# LB_BIT_1IN_1OUT-XXLWIDE-v03_1_1x.net
KiCad netlist of a schematic drawn in EAGLE
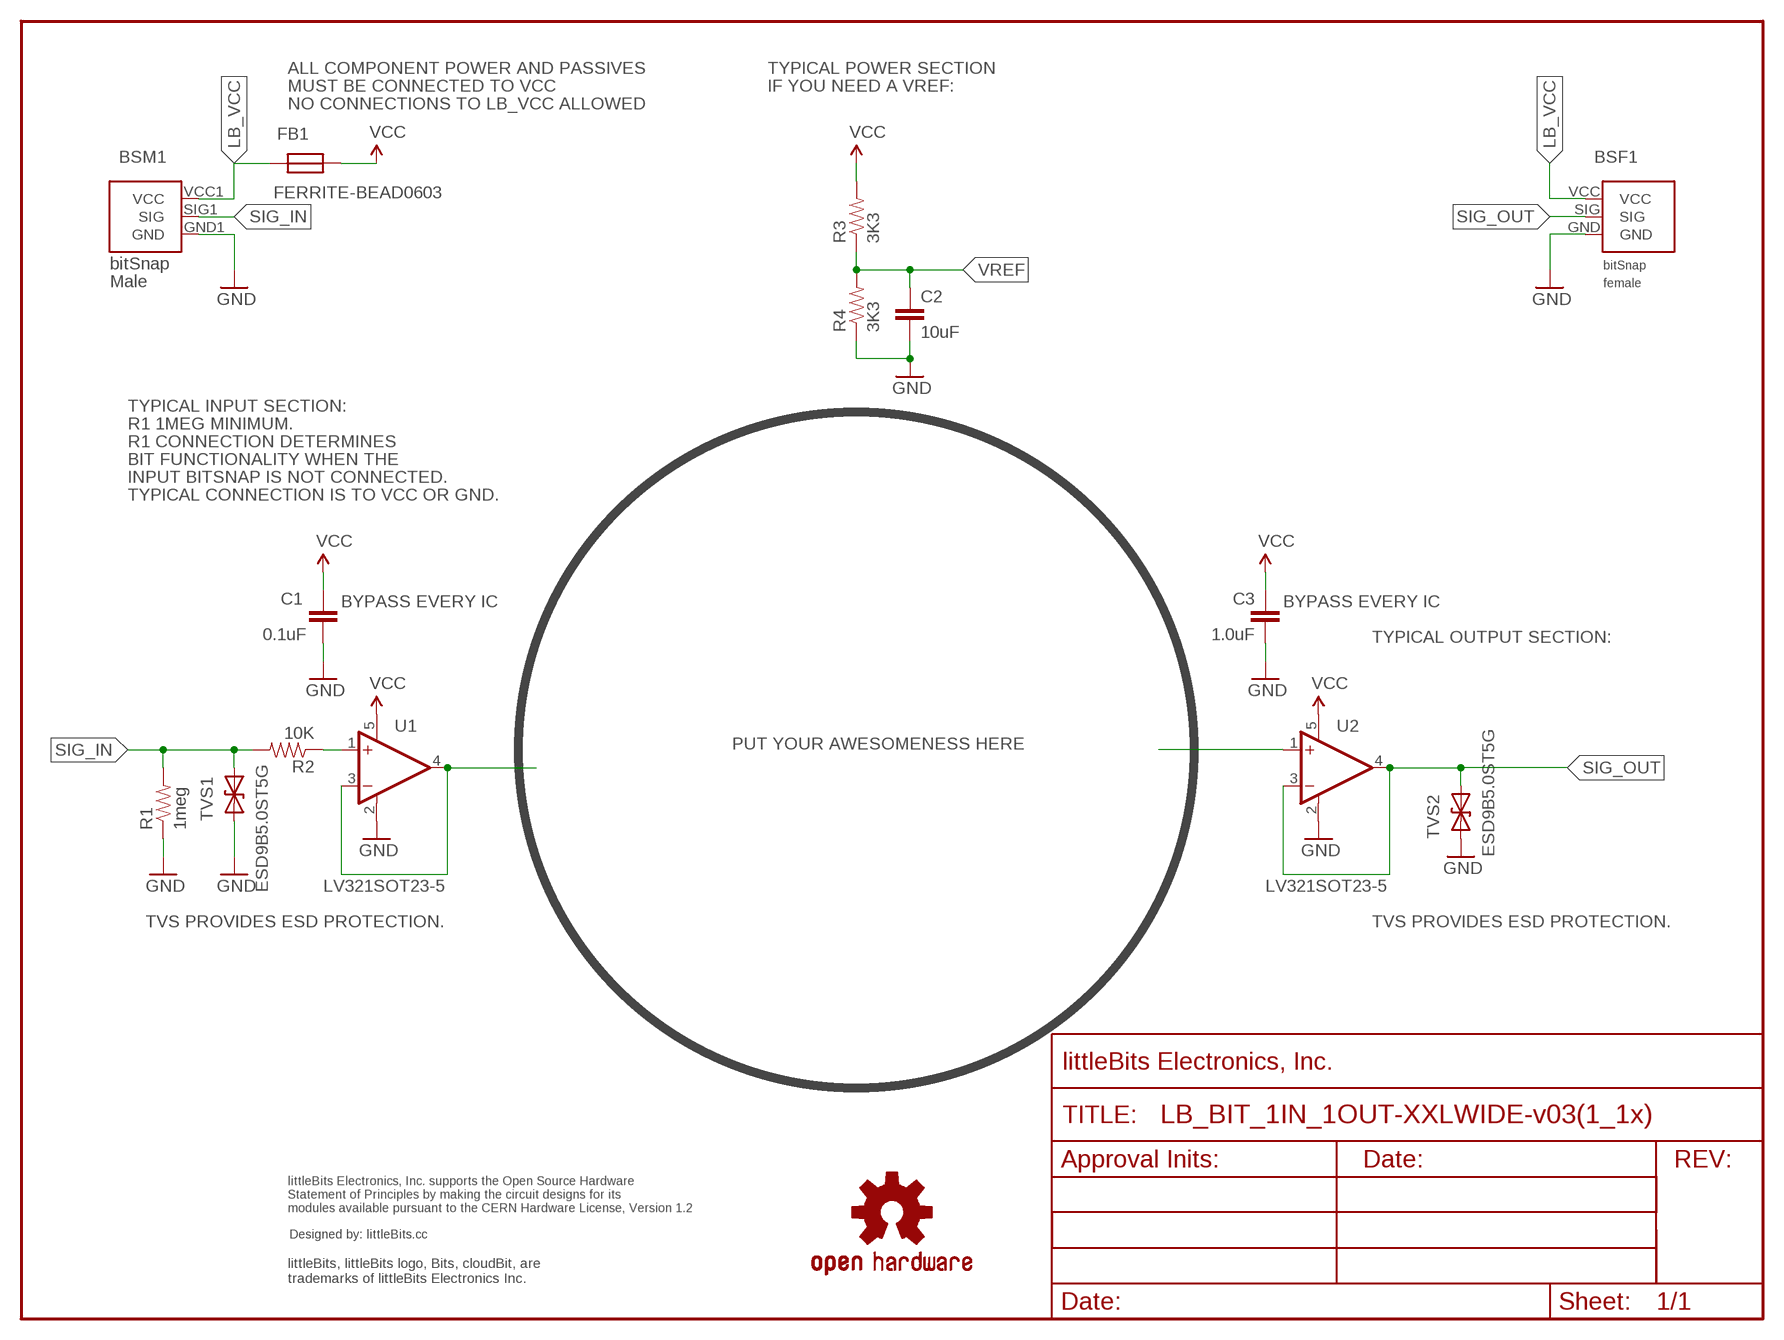
[diagram p0: schematic, sheet 1]

(export (version "E")
  (design (tool "Eeschema 10.0.6"))
  (components
    (comp (ref "BSF1")
      (value "BITSNAP_V03_FEMALE")
      (footprint "eagle-import:BITSNAP_V03_FEMALE")
      (libsource (lib "eagle-import") (part "BITSNAP_V03_FEMALE"))
    )
    (comp (ref "BSM1")
      (value "BITSNAP_V03_MALE")
      (footprint "eagle-import:BITSNAP_V03_MALE")
      (libsource (lib "eagle-import") (part "BITSNAP_V03_MALE"))
    )
    (comp (ref "C1")
      (value "0.1uF")
      (footprint "eagle-import:CAP-0603")
      (libsource (lib "eagle-import") (part "CAPCAP-0603"))
    )
    (comp (ref "C2")
      (value "10uF")
      (footprint "eagle-import:CAP-0603")
      (libsource (lib "eagle-import") (part "CAPCAP-0603"))
    )
    (comp (ref "C3")
      (value "1.0uF")
      (footprint "eagle-import:CAP-0603")
      (libsource (lib "eagle-import") (part "CAPCAP-0603"))
    )
    (comp (ref "FB1")
      (value "FERRITE-BEAD0603")
      (footprint "eagle-import:R0603")
      (libsource (lib "eagle-import") (part "FERRITE-BEAD0603"))
    )
    (comp (ref "R1")
      (value "1meg")
      (footprint "eagle-import:RES-0603")
      (libsource (lib "eagle-import") (part "RESISTOR0603"))
    )
    (comp (ref "R2")
      (value "10K")
      (footprint "eagle-import:RES-0603")
      (libsource (lib "eagle-import") (part "RESISTOR0603"))
    )
    (comp (ref "R3")
      (value "3K3")
      (footprint "eagle-import:RES-0603")
      (libsource (lib "eagle-import") (part "RESISTOR0603"))
    )
    (comp (ref "R4")
      (value "3K3")
      (footprint "eagle-import:RES-0603")
      (libsource (lib "eagle-import") (part "RESISTOR0603"))
    )
    (comp (ref "TVS1")
      (value "ESD9B5.0ST5G")
      (footprint "eagle-import:SOD-923")
      (libsource (lib "eagle-import") (part "DIODE-TVSSOD-923"))
    )
    (comp (ref "TVS2")
      (value "ESD9B5.0ST5G")
      (footprint "eagle-import:SOD-923")
      (libsource (lib "eagle-import") (part "DIODE-TVSSOD-923"))
    )
    (comp (ref "U$1")
      (value "OSHW-LOGOL")
      (footprint "eagle-import:OSHW-LOGO-L")
      (libsource (lib "eagle-import") (part "OSHW-LOGOL"))
    )
    (comp (ref "U$2")
      (value "OSHWCREDIT")
      (footprint "eagle-import:OSHWCREDIT")
      (libsource (lib "eagle-import") (part "OSHWCREDIT"))
    )
    (comp (ref "U$5")
      (value "FRAME-LETTER-OHWOHW")
      (footprint "eagle-import:FABDWG01-OHW")
      (libsource (lib "eagle-import") (part "FRAME-LETTER-OHWOHW"))
    )
    (comp (ref "U1")
      (value "LV321SOT23-5")
      (footprint "eagle-import:SOT23-5")
      (libsource (lib "eagle-import") (part "LV321SOT23-5"))
    )
    (comp (ref "U2")
      (value "LV321SOT23-5")
      (footprint "eagle-import:SOT23-5")
      (libsource (lib "eagle-import") (part "LV321SOT23-5"))
    )
  )
  (nets
    (net (code "1") (name "GND") (class "Default")
      (node (ref "BSF1") (pin "GND") (pinfunction "GND_GND") (pintype "bidirectional"))
      (node (ref "BSM1") (pin "GND1") (pinfunction "GND_GND1") (pintype "bidirectional"))
      (node (ref "C1") (pin "2") (pinfunction "2_2") (pintype "passive"))
      (node (ref "C2") (pin "2") (pinfunction "2_2") (pintype "passive"))
      (node (ref "C3") (pin "1") (pinfunction "1_1") (pintype "passive"))
      (node (ref "R1") (pin "1") (pinfunction "1_1") (pintype "passive"))
      (node (ref "R4") (pin "1") (pinfunction "1_1") (pintype "passive"))
      (node (ref "TVS1") (pin "1") (pinfunction "A_1") (pintype "passive"))
      (node (ref "TVS2") (pin "1") (pinfunction "A_1") (pintype "passive"))
      (node (ref "U1") (pin "2") (pinfunction "V-_2") (pintype "power_in"))
      (node (ref "U2") (pin "2") (pinfunction "V-_2") (pintype "power_in"))
    )
    (net (code "2") (name "LB_VCC") (class "Default")
      (node (ref "BSF1") (pin "VCC") (pinfunction "VCC_VCC") (pintype "bidirectional"))
      (node (ref "BSM1") (pin "VCC1") (pinfunction "VCC_VCC1") (pintype "bidirectional"))
      (node (ref "FB1") (pin "2") (pinfunction "P$2_2") (pintype "bidirectional"))
    )
    (net (code "3") (name "Net-(U1-+IN)") (class "Default")
      (node (ref "R2") (pin "1") (pinfunction "1_1") (pintype "passive"))
      (node (ref "U1") (pin "1") (pinfunction "+IN_1") (pintype "input"))
    )
    (net (code "4") (name "Net-(U1--IN)") (class "Default")
      (node (ref "U1") (pin "3") (pinfunction "-IN_3") (pintype "input"))
      (node (ref "U1") (pin "4") (pinfunction "OUT_4") (pintype "output"))
    )
    (net (code "5") (name "SIG_IN") (class "Default")
      (node (ref "BSM1") (pin "SIG1") (pinfunction "SIG_SIG1") (pintype "bidirectional"))
      (node (ref "R1") (pin "2") (pinfunction "2_2") (pintype "passive"))
      (node (ref "R2") (pin "2") (pinfunction "2_2") (pintype "passive"))
      (node (ref "TVS1") (pin "2") (pinfunction "C_2") (pintype "passive"))
    )
    (net (code "6") (name "SIG_OUT") (class "Default")
      (node (ref "BSF1") (pin "SIG") (pinfunction "SIG_SIG") (pintype "bidirectional"))
      (node (ref "TVS2") (pin "2") (pinfunction "C_2") (pintype "passive"))
      (node (ref "U2") (pin "3") (pinfunction "-IN_3") (pintype "input"))
      (node (ref "U2") (pin "4") (pinfunction "OUT_4") (pintype "output"))
    )
    (net (code "7") (name "VCC") (class "Default")
      (node (ref "C1") (pin "1") (pinfunction "1_1") (pintype "passive"))
      (node (ref "C3") (pin "2") (pinfunction "2_2") (pintype "passive"))
      (node (ref "FB1") (pin "1") (pinfunction "P$1_1") (pintype "bidirectional"))
      (node (ref "R3") (pin "2") (pinfunction "2_2") (pintype "passive"))
      (node (ref "U1") (pin "5") (pinfunction "V+_5") (pintype "power_in"))
      (node (ref "U2") (pin "5") (pinfunction "V+_5") (pintype "power_in"))
    )
    (net (code "8") (name "VREF") (class "Default")
      (node (ref "C2") (pin "1") (pinfunction "1_1") (pintype "passive"))
      (node (ref "R3") (pin "1") (pinfunction "1_1") (pintype "passive"))
      (node (ref "R4") (pin "2") (pinfunction "2_2") (pintype "passive"))
    )
    (net (code "9") (name "unconnected-(U2-+IN-Pad1)") (class "Default")
      (node (ref "U2") (pin "1") (pinfunction "+IN_1") (pintype "input"))
    )
  )
)
